# MCP1640.net
KiCad netlist of a schematic drawn in EAGLE
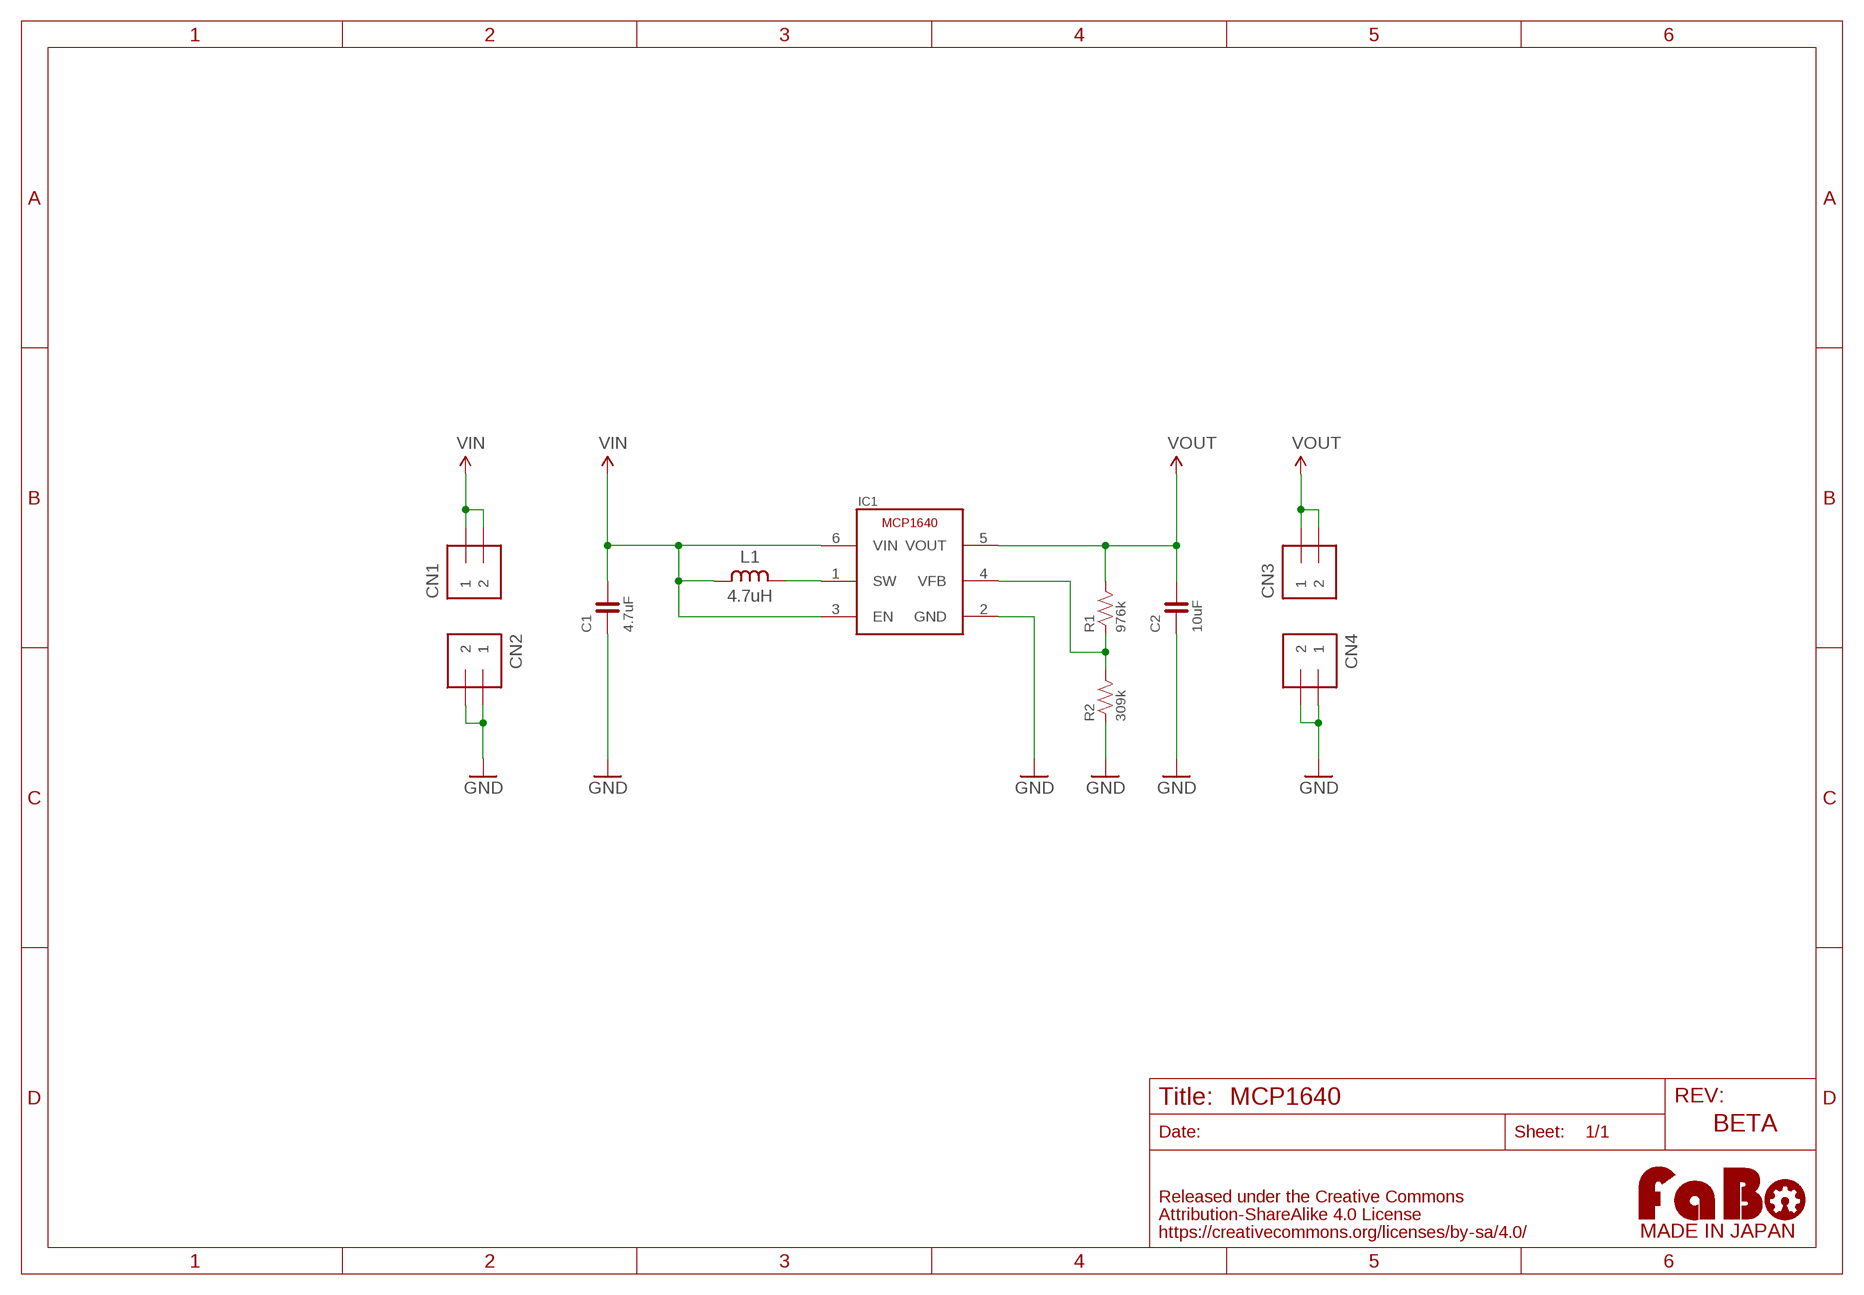
[diagram p0: schematic, sheet 1]

(export (version "E")
  (design (tool "Eeschema 10.0.6"))
  (components
    (comp (ref "C1")
      (value "4.7uF")
      (footprint "eagle-import:0603-NARROW")
      (libsource (lib "eagle-import") (part "CAPACITOR-0603_NARROW"))
    )
    (comp (ref "C2")
      (value "10uF")
      (footprint "eagle-import:0603-NARROW")
      (libsource (lib "eagle-import") (part "CAPACITOR-0603_NARROW"))
    )
    (comp (ref "CN1")
      (value "PIN_HEADER_1X2")
      (footprint "eagle-import:PIN_1X2")
      (libsource (lib "eagle-import") (part "PIN_HEADER_1X2"))
    )
    (comp (ref "CN2")
      (value "PIN_HEADER_1X2")
      (footprint "eagle-import:PIN_1X2")
      (libsource (lib "eagle-import") (part "PIN_HEADER_1X2"))
    )
    (comp (ref "CN3")
      (value "PIN_HEADER_1X2")
      (footprint "eagle-import:PIN_1X2")
      (libsource (lib "eagle-import") (part "PIN_HEADER_1X2"))
    )
    (comp (ref "CN4")
      (value "PIN_HEADER_1X2")
      (footprint "eagle-import:PIN_1X2")
      (libsource (lib "eagle-import") (part "PIN_HEADER_1X2"))
    )
    (comp (ref "IC1")
      (value "MCP1640T")
      (footprint "eagle-import:SOT-23-6")
      (libsource (lib "eagle-import") (part "MCP1640T"))
    )
    (comp (ref "L1")
      (value "4.7uH")
      (footprint "eagle-import:LQH3NPN")
      (libsource (lib "eagle-import") (part "INDUCTOR-LQH3NPN"))
    )
    (comp (ref "R1")
      (value "976k")
      (footprint "eagle-import:0603-NARROW")
      (libsource (lib "eagle-import") (part "RESISTOR-0603-NARROW"))
    )
    (comp (ref "R2")
      (value "309k")
      (footprint "eagle-import:0603-NARROW")
      (libsource (lib "eagle-import") (part "RESISTOR-0603-NARROW"))
    )
    (comp (ref "U$2")
      (value "LOGO_FABO-M_BOTTOM")
      (footprint "eagle-import:LOGO_FABO_MS_BOTTOM")
      (libsource (lib "eagle-import") (part "LOGO_FABO-M_BOTTOM"))
    )
  )
  (nets
    (net (code "1") (name "GND") (class "Default")
      (node (ref "C1") (pin "1") (pinfunction "1_1") (pintype "passive"))
      (node (ref "C2") (pin "1") (pinfunction "1_1") (pintype "passive"))
      (node (ref "CN2") (pin "1") (pinfunction "1_1") (pintype "bidirectional"))
      (node (ref "CN2") (pin "2") (pinfunction "2_2") (pintype "bidirectional"))
      (node (ref "CN4") (pin "1") (pinfunction "1_1") (pintype "bidirectional"))
      (node (ref "CN4") (pin "2") (pinfunction "2_2") (pintype "bidirectional"))
      (node (ref "IC1") (pin "2") (pinfunction "GND_2") (pintype "bidirectional"))
      (node (ref "R2") (pin "1") (pinfunction "1_1") (pintype "bidirectional"))
    )
    (net (code "2") (name "Net-(IC1-SW)") (class "Default")
      (node (ref "IC1") (pin "1") (pinfunction "SW_1") (pintype "bidirectional"))
      (node (ref "L1") (pin "2") (pinfunction "2_2") (pintype "bidirectional"))
    )
    (net (code "3") (name "Net-(IC1-VFB)") (class "Default")
      (node (ref "IC1") (pin "4") (pinfunction "VFB_4") (pintype "bidirectional"))
      (node (ref "R1") (pin "1") (pinfunction "1_1") (pintype "bidirectional"))
      (node (ref "R2") (pin "2") (pinfunction "2_2") (pintype "bidirectional"))
    )
    (net (code "4") (name "VIN") (class "Default")
      (node (ref "C1") (pin "2") (pinfunction "2_2") (pintype "passive"))
      (node (ref "CN1") (pin "1") (pinfunction "1_1") (pintype "bidirectional"))
      (node (ref "CN1") (pin "2") (pinfunction "2_2") (pintype "bidirectional"))
      (node (ref "IC1") (pin "3") (pinfunction "EN_3") (pintype "bidirectional"))
      (node (ref "IC1") (pin "6") (pinfunction "VIN_6") (pintype "bidirectional"))
      (node (ref "L1") (pin "1") (pinfunction "1_1") (pintype "bidirectional"))
    )
    (net (code "5") (name "VOUT") (class "Default")
      (node (ref "C2") (pin "2") (pinfunction "2_2") (pintype "passive"))
      (node (ref "CN3") (pin "1") (pinfunction "1_1") (pintype "bidirectional"))
      (node (ref "CN3") (pin "2") (pinfunction "2_2") (pintype "bidirectional"))
      (node (ref "IC1") (pin "5") (pinfunction "VOUT_5") (pintype "bidirectional"))
      (node (ref "R1") (pin "2") (pinfunction "2_2") (pintype "bidirectional"))
    )
  )
)
